# 5_to_3_3_Level_Converter.net
KiCad netlist of a schematic drawn in EAGLE
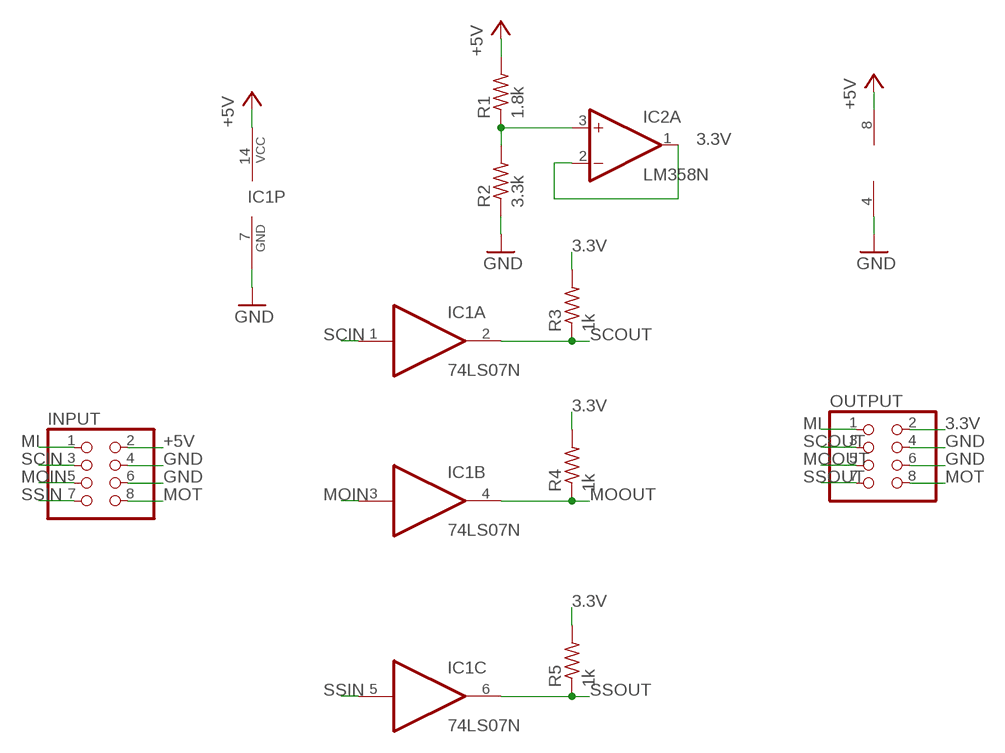
[diagram p0: schematic, sheet 1]

(export (version "E")
  (design (tool "Eeschema 10.0.6"))
  (components
    (comp (ref "IC1")
      (value "74LS07N")
      (footprint "eagle-import:DIL14")
      (libsource (lib "eagle-import") (part "7407NLS"))
    )
    (comp (ref "IC2")
      (value "LM358N")
      (footprint "eagle-import:DIL08")
      (libsource (lib "eagle-import") (part "LM358N"))
    )
    (comp (ref "INPUT")
      (value "PINHD-2X4")
      (footprint "eagle-import:2X04")
      (libsource (lib "eagle-import") (part "PINHD-2X4"))
    )
    (comp (ref "OUTPUT")
      (value "PINHD-2X4")
      (footprint "eagle-import:2X04")
      (libsource (lib "eagle-import") (part "PINHD-2X4"))
    )
    (comp (ref "R1")
      (value "1.8k")
      (footprint "eagle-import:0207_7")
      (libsource (lib "eagle-import") (part "R-US_0207/7"))
    )
    (comp (ref "R2")
      (value "3.3k")
      (footprint "eagle-import:0207_7")
      (libsource (lib "eagle-import") (part "R-US_0207/7"))
    )
    (comp (ref "R3")
      (value "1k")
      (footprint "eagle-import:0207_7")
      (libsource (lib "eagle-import") (part "R-US_0207/7"))
    )
    (comp (ref "R4")
      (value "1k")
      (footprint "eagle-import:0207_7")
      (libsource (lib "eagle-import") (part "R-US_0207/7"))
    )
    (comp (ref "R5")
      (value "1k")
      (footprint "eagle-import:0207_7")
      (libsource (lib "eagle-import") (part "R-US_0207/7"))
    )
  )
  (nets
    (net (code "1") (name "+5V") (class "Default")
      (node (ref "IC1") (pin "14") (pinfunction "VCC_14") (pintype "power_in"))
      (node (ref "IC2") (pin "8") (pinfunction "V+_8") (pintype "power_in"))
      (node (ref "INPUT") (pin "2") (pinfunction "2_2") (pintype "passive"))
      (node (ref "R1") (pin "2") (pinfunction "2_2") (pintype "passive"))
    )
    (net (code "2") (name "/3.3V") (class "Default")
      (node (ref "IC2") (pin "1") (pinfunction "OUT_1") (pintype "output"))
      (node (ref "IC2") (pin "2") (pinfunction "-IN_2") (pintype "input"))
      (node (ref "OUTPUT") (pin "2") (pinfunction "2_2") (pintype "passive"))
      (node (ref "R3") (pin "2") (pinfunction "2_2") (pintype "passive"))
      (node (ref "R4") (pin "2") (pinfunction "2_2") (pintype "passive"))
      (node (ref "R5") (pin "2") (pinfunction "2_2") (pintype "passive"))
    )
    (net (code "3") (name "/MI") (class "Default")
      (node (ref "INPUT") (pin "1") (pinfunction "1_1") (pintype "passive"))
      (node (ref "OUTPUT") (pin "1") (pinfunction "1_1") (pintype "passive"))
    )
    (net (code "4") (name "/MOIN") (class "Default")
      (node (ref "IC1") (pin "3") (pinfunction "I_3") (pintype "input"))
      (node (ref "INPUT") (pin "5") (pinfunction "5_5") (pintype "passive"))
    )
    (net (code "5") (name "/MOOUT") (class "Default")
      (node (ref "IC1") (pin "4") (pinfunction "O_4") (pintype "open_collector"))
      (node (ref "OUTPUT") (pin "5") (pinfunction "5_5") (pintype "passive"))
      (node (ref "R4") (pin "1") (pinfunction "1_1") (pintype "passive"))
    )
    (net (code "6") (name "/MOT") (class "Default")
      (node (ref "INPUT") (pin "8") (pinfunction "8_8") (pintype "passive"))
      (node (ref "OUTPUT") (pin "8") (pinfunction "8_8") (pintype "passive"))
    )
    (net (code "7") (name "/SCIN") (class "Default")
      (node (ref "IC1") (pin "1") (pinfunction "I_1") (pintype "input"))
      (node (ref "INPUT") (pin "3") (pinfunction "3_3") (pintype "passive"))
    )
    (net (code "8") (name "/SCOUT") (class "Default")
      (node (ref "IC1") (pin "2") (pinfunction "O_2") (pintype "open_collector"))
      (node (ref "OUTPUT") (pin "3") (pinfunction "3_3") (pintype "passive"))
      (node (ref "R3") (pin "1") (pinfunction "1_1") (pintype "passive"))
    )
    (net (code "9") (name "/SSIN") (class "Default")
      (node (ref "IC1") (pin "5") (pinfunction "I_5") (pintype "input"))
      (node (ref "INPUT") (pin "7") (pinfunction "7_7") (pintype "passive"))
    )
    (net (code "10") (name "/SSOUT") (class "Default")
      (node (ref "IC1") (pin "6") (pinfunction "O_6") (pintype "open_collector"))
      (node (ref "OUTPUT") (pin "7") (pinfunction "7_7") (pintype "passive"))
      (node (ref "R5") (pin "1") (pinfunction "1_1") (pintype "passive"))
    )
    (net (code "11") (name "GND") (class "Default")
      (node (ref "IC1") (pin "7") (pinfunction "GND_7") (pintype "power_in"))
      (node (ref "IC2") (pin "4") (pinfunction "V-_4") (pintype "power_in"))
      (node (ref "INPUT") (pin "4") (pinfunction "4_4") (pintype "passive"))
      (node (ref "INPUT") (pin "6") (pinfunction "6_6") (pintype "passive"))
      (node (ref "OUTPUT") (pin "4") (pinfunction "4_4") (pintype "passive"))
      (node (ref "OUTPUT") (pin "6") (pinfunction "6_6") (pintype "passive"))
      (node (ref "R2") (pin "1") (pinfunction "1_1") (pintype "passive"))
    )
    (net (code "12") (name "Net-(IC2A-+IN)") (class "Default")
      (node (ref "IC2") (pin "3") (pinfunction "+IN_3") (pintype "input"))
      (node (ref "R1") (pin "1") (pinfunction "1_1") (pintype "passive"))
      (node (ref "R2") (pin "2") (pinfunction "2_2") (pintype "passive"))
    )
  )
)
